# Schaltplan.net
KiCad netlist of a schematic drawn in EAGLE
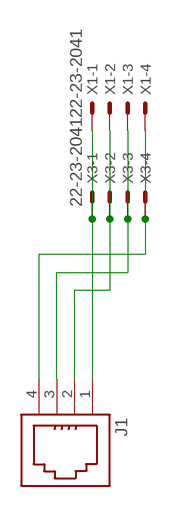
[diagram p0: schematic, sheet 1]

(export (version "E")
  (design (tool "Eeschema 10.0.6"))
  (components
    (comp (ref "J1")
      (value "615004143821")
      (footprint "eagle-import:615004143821")
      (libsource (lib "eagle-import") (part "615004143821"))
    )
    (comp (ref "X1")
      (value "22-23-2041")
      (footprint "eagle-import:22-23-2041")
      (fields (field (name "MF") "MOLEX"))
      (libsource (lib "eagle-import") (part "22-23-2041"))
    )
    (comp (ref "X3")
      (value "22-23-2041")
      (footprint "eagle-import:22-23-2041")
      (fields (field (name "MF") "MOLEX"))
      (libsource (lib "eagle-import") (part "22-23-2041"))
    )
  )
  (nets
    (net (code "1") (name "Net-(J1-1)") (class "Default")
      (node (ref "J1") (pin "4") (pinfunction "1_4") (pintype "passive"))
      (node (ref "X1") (pin "4") (pinfunction "S_4") (pintype "passive"))
      (node (ref "X3") (pin "4") (pinfunction "S_4") (pintype "passive"))
    )
    (net (code "2") (name "Net-(J1-2)") (class "Default")
      (node (ref "J1") (pin "3") (pinfunction "2_3") (pintype "passive"))
      (node (ref "X1") (pin "3") (pinfunction "S_3") (pintype "passive"))
      (node (ref "X3") (pin "3") (pinfunction "S_3") (pintype "passive"))
    )
    (net (code "3") (name "Net-(J1-3)") (class "Default")
      (node (ref "J1") (pin "2") (pinfunction "3_2") (pintype "passive"))
      (node (ref "X1") (pin "2") (pinfunction "S_2") (pintype "passive"))
      (node (ref "X3") (pin "2") (pinfunction "S_2") (pintype "passive"))
    )
    (net (code "4") (name "Net-(J1-4)") (class "Default")
      (node (ref "J1") (pin "1") (pinfunction "4_1") (pintype "passive"))
      (node (ref "X1") (pin "1") (pinfunction "S_1") (pintype "passive"))
      (node (ref "X3") (pin "1") (pinfunction "S_1") (pintype "passive"))
    )
  )
)
